# hbrigde.net
KiCad netlist of a schematic drawn in EAGLE
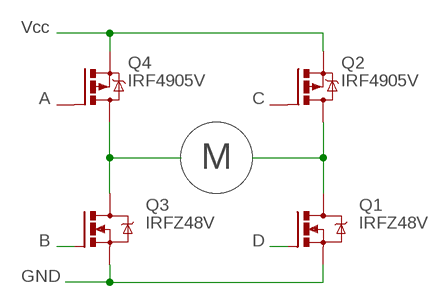
[diagram p0: schematic, sheet 1]

(export (version "E")
  (design (tool "Eeschema 10.0.6"))
  (components
    (comp (ref "Q1")
      (value "IRFZ48V")
      (footprint "eagle-import:TO220BV")
      (libsource (lib "eagle-import") (part "IRFZ48V"))
    )
    (comp (ref "Q2")
      (value "IRF4905V")
      (footprint "eagle-import:TO220BV")
      (libsource (lib "eagle-import") (part "IRF4905V"))
    )
    (comp (ref "Q3")
      (value "IRFZ48V")
      (footprint "eagle-import:TO220BV")
      (libsource (lib "eagle-import") (part "IRFZ48V"))
    )
    (comp (ref "Q4")
      (value "IRF4905V")
      (footprint "eagle-import:TO220BV")
      (libsource (lib "eagle-import") (part "IRF4905V"))
    )
  )
  (nets
    (net (code "1") (name "Net-(Q1-PadD)") (class "Default")
      (node (ref "Q1") (pin "D") (pinfunction "D_D") (pintype "passive"))
      (node (ref "Q2") (pin "D") (pinfunction "D_D") (pintype "passive"))
    )
    (net (code "2") (name "Net-(Q1-PadS)") (class "Default")
      (node (ref "Q1") (pin "S") (pinfunction "S_S") (pintype "passive"))
      (node (ref "Q3") (pin "S") (pinfunction "S_S") (pintype "passive"))
    )
    (net (code "3") (name "Net-(Q2-PadS)") (class "Default")
      (node (ref "Q2") (pin "S") (pinfunction "S_S") (pintype "passive"))
      (node (ref "Q4") (pin "S") (pinfunction "S_S") (pintype "passive"))
    )
    (net (code "4") (name "Net-(Q3-PadD)") (class "Default")
      (node (ref "Q3") (pin "D") (pinfunction "D_D") (pintype "passive"))
      (node (ref "Q4") (pin "D") (pinfunction "D_D") (pintype "passive"))
    )
    (net (code "5") (name "unconnected-(Q1-PadG)") (class "Default")
      (node (ref "Q1") (pin "G") (pinfunction "G_G") (pintype "passive"))
    )
    (net (code "6") (name "unconnected-(Q2-PadG)") (class "Default")
      (node (ref "Q2") (pin "G") (pinfunction "G_G") (pintype "passive"))
    )
    (net (code "7") (name "unconnected-(Q3-PadG)") (class "Default")
      (node (ref "Q3") (pin "G") (pinfunction "G_G") (pintype "passive"))
    )
    (net (code "8") (name "unconnected-(Q4-PadG)") (class "Default")
      (node (ref "Q4") (pin "G") (pinfunction "G_G") (pintype "passive"))
    )
  )
)
